# Power_Delivery.net
KiCad netlist of a schematic drawn in Altium Designer
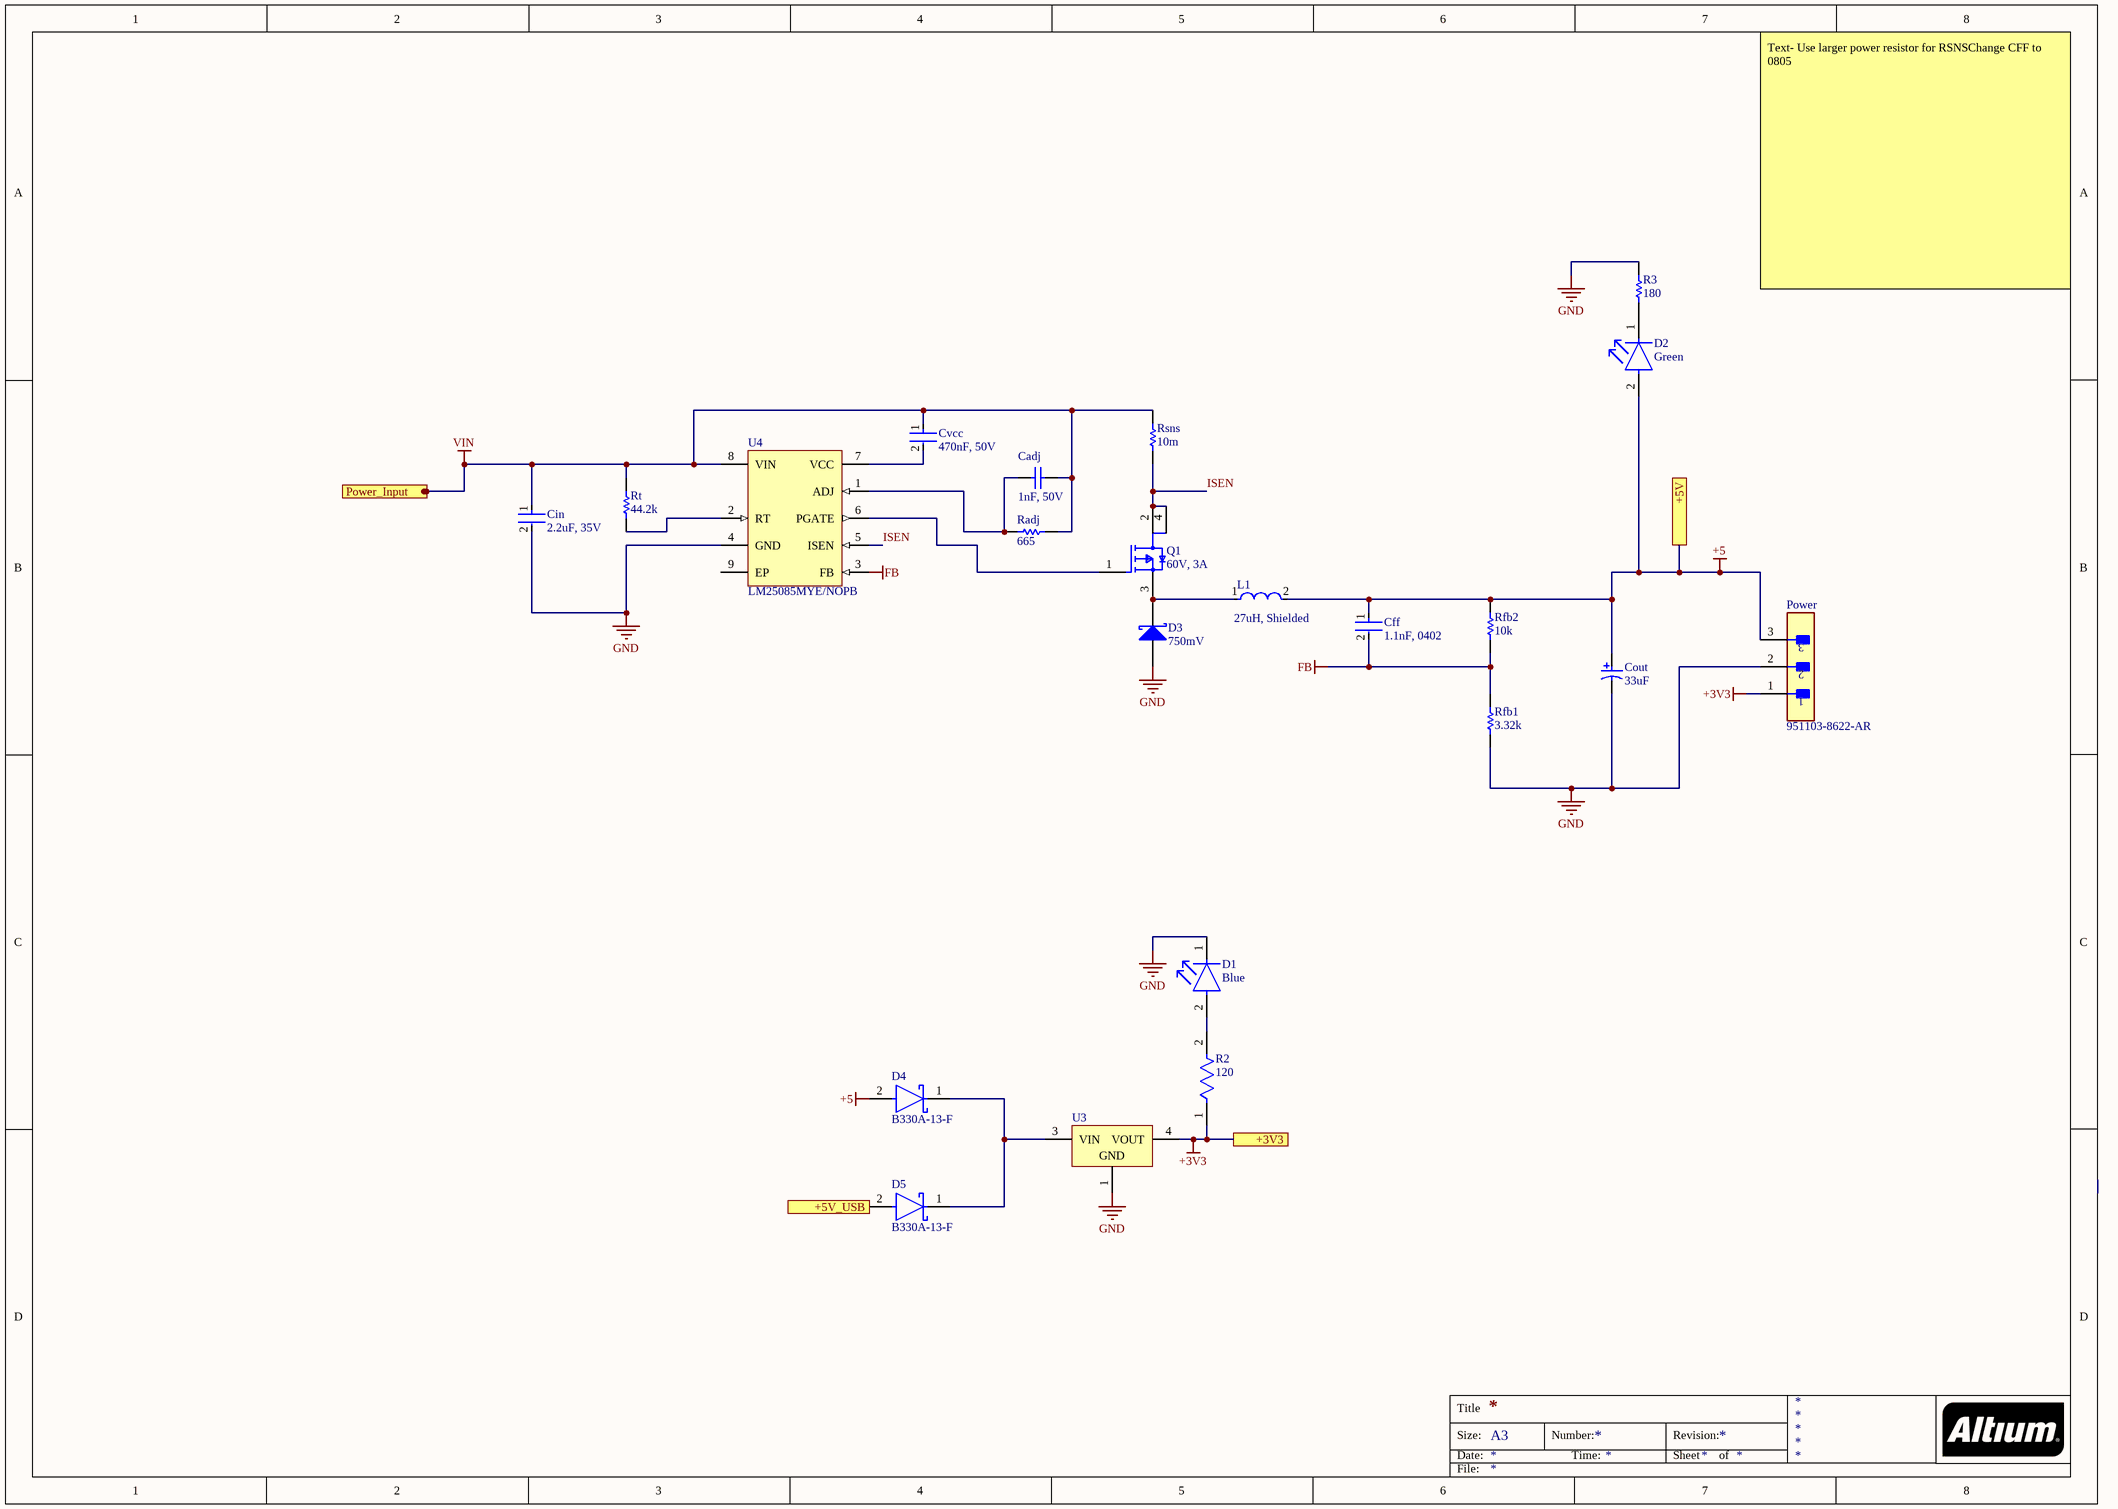
[diagram p0: Power Delivery.SchDoc]

(export (version "E")
  (design (tool "Eeschema 10.0.6"))
  (components
    (comp (ref "Cadj")
      (value "1nF, 50V")
      (footprint "CAPC2013X94X50ML20T25")
      (fields
        (field (name "PART NUMBER") "08055F102KAT2A")
        (field (name "MANUFACTURER") "AVX Interconnect / Elco")
      )
      (libsource (lib "Altium Content Vault") (part "CAP"))
    )
    (comp (ref "Cff")
      (value "1.1nF, 0402")
      (footprint "FP-C0402-BB-MFG")
      (description "CAP CER 1100PF 50V C0G/NP0 0402")
      (fields (field (name "MANUFACTURER PART NUMBER") "C0402C112J5GACTU") (field (name "TOLERANCE") "0.05"))
      (libsource (lib "Altium Content Vault") (part "b4654b650e69147ec39a6b967a45e02"))
    )
    (comp (ref "Cin")
      (value "2.2uF, 35V")
      (footprint "FP-C2012-125-0_2-IPC_B")
      (description "Multilayer Ceramic Capacitors 2.2μF ±10% 35V X6S SMD 0805")
      (fields (field (name "TOLERANCE") "10%"))
      (libsource (lib "Altium Content Vault") (part "b4654b650e69147ec39a6b967a45e02"))
    )
    (comp (ref "Cout")
      (value "33uF")
      (footprint "NIC-CAPA2-6.3X5.8_V")
      (fields (field (name "PARTNUMBER") "UUD1C330MCL1GS") (field (name "MANUFACTURER") "Nichicon"))
      (libsource (lib "Altium Content Vault") (part "NIC-CAP-P-2"))
    )
    (comp (ref "Cvcc")
      (value "470nF, 50V")
      (footprint "FP-GCM21B-0_15-IPC_A")
      (description "Ceramic Capacitor for Automotive 470nF ±10% 50VDC X7R 0805 Embossed T/R")
      (fields (field (name "TOLERANCE") "10%"))
      (libsource (lib "Altium Content Vault") (part "02cd4be3c70576c341d710602a673aa"))
    )
    (comp (ref "D1")
      (value "Blue")
      (footprint "FP-LTST-C191TBKT-MFG")
      (description "LED BLUE CLEAR CHIP SMD")
      (libsource (lib "Altium Content Vault") (part "8706943c75ba83719d021d2fdc84c58"))
    )
    (comp (ref "D2")
      (value "Green")
      (footprint "FP-6_541-5056_01-4-MFG")
      (description "LED GREEN 0603 SMD")
      (fields
        (field (name "MANUFACTURER PART NUMBER") "TLMP1100-GS08")
        (field (name "MANUFACTURER") "Vishay")
      )
      (libsource (lib "Altium Content Vault") (part "8706943c75ba83719d021d2fdc84c58"))
    )
    (comp (ref "D3")
      (value "750mV")
      (footprint "DIOD-SOD-323-2_V")
      (description "Schottky Barrier Diode, 30 V, -65 to 150 degC, 2-Pin SOD-323, RoHS, Tape and Reel")
      (fields (field (name "MANUFACTURER") "DiodesIncorporated"))
      (libsource (lib "Altium Content Vault") (part "DSKY-AK-2"))
    )
    (comp (ref "D4")
      (value "B330A-13-F")
      (footprint "FP-SMA-MFG")
      (description "DIODE SCHOTTKY 30V 3A SMA")
      (fields
        (field (name "OCTOPART") "https://octopart.com/b330a-13-f-diodes+inc.-325808")
        (field (name "MANUFACTURER") "Diodes")
      )
      (libsource (lib "Altium Content Vault") (part "1d6ec82d83fb6aee721767c19dac4b9"))
    )
    (comp (ref "D5")
      (value "B330A-13-F")
      (footprint "FP-SMA-MFG")
      (description "DIODE SCHOTTKY 30V 3A SMA")
      (fields
        (field (name "OCTOPART") "https://octopart.com/b330a-13-f-diodes+inc.-325808")
        (field (name "MANUFACTURER") "Diodes")
      )
      (libsource (lib "Altium Content Vault") (part "1d6ec82d83fb6aee721767c19dac4b9"))
    )
    (comp (ref "L1")
      (value "27uH, Shielded")
      (footprint "FP-SRR1260-MFG")
      (description "FIXED IND 27UH 3.6A 45 MOHM SMD")
      (fields (field (name "TOLERANCE") "20%") (field (name "MANUFACTURER PART NUMBER") "SRR1260-270M"))
      (libsource (lib "Altium Content Vault") (part "725321dda6339637d4d059423bc1c3c"))
    )
    (comp (ref "Power")
      (value "951103-8622-AR")
      (footprint "FP-951103-8622-AR-MFG")
      (description "CONN HEADER VERT 3POS 2MM")
      (fields
        (field (name "OCTOPART") "https://octopart.com/951103-8622-ar-3m-14400669")
        (field (name "MANUFACTURER") "3M")
      )
      (libsource (lib "Altium Content Vault") (part "0d3f023dd272f625e17a2be33dea85f"))
    )
    (comp (ref "Q1")
      (value "60V, 3A")
      (footprint "FP-SOT223-IPC_C")
      (description "MOSFET PCH 60V 3A SOT223")
      (libsource (lib "Altium Content Vault") (part "d648c27f595ee349eac043f81b2e06c"))
    )
    (comp (ref "R2")
      (value "120")
      (footprint "FP-AC0805-MFG")
      (description "RES SMD 120 OHM 5% 1/8W 0805")
      (fields
        (field (name "OCTOPART") "https://octopart.com/ac0805jr-07120rl-yageo-52448213")
        (field (name "TOLERANCE") "0.05")
      )
      (libsource (lib "Altium Content Vault") (part "1029c3af85768c4190bb7ad29bc67b5"))
    )
    (comp (ref "R3")
      (value "180")
      (footprint "RESC2013X70X40ML20T20")
      (fields (field (name "MANUFACTURER") "Panasonic") (field (name "PART NUMBER") "ERJ-6GEYJ181V"))
      (libsource (lib "Altium Content Vault") (part "RES"))
    )
    (comp (ref "Radj")
      (value "665")
      (footprint "RESC2013X70X40LL20T20")
      (description "Chip Resistor, 665 Ohm, +/- 1%, 0.125 W, -55 to 155 degC, 0805 (2012 Metric), RoHS, Tape and Reel")
      (fields (field (name "MANUFACTURER") "Panasonic"))
      (libsource (lib "Altium Content Vault") (part "RES-2"))
    )
    (comp (ref "Rfb1")
      (value "3.32k")
      (footprint "RESC2013X55X40NL15T20")
      (fields (field (name "PART NUMBER") "TNPW08053K32BEEN") (field (name "MANUFACTURER") "Vishay Dale"))
      (libsource (lib "Altium Content Vault") (part "RES"))
    )
    (comp (ref "Rfb2")
      (value "10k")
      (footprint "RESC2013X60X35NL10T20")
      (description "Chip Resistor, 10 KOhm, +/- 1%, 0.125 W, -55 to 155 degC, 0805 (2012 Metric), RoHS, Tape and Reel")
      (fields (field (name "MANUFACTURER") "Yageo"))
      (libsource (lib "Altium Content Vault") (part "RES-2"))
    )
    (comp (ref "Rsns")
      (value "10m")
      (footprint "RESC2013X60X35LL10T20")
      (fields (field (name "PART NUMBER") "RL0805FR-070R01L") (field (name "MANUFACTURER") "Yageo"))
      (libsource (lib "Altium Content Vault") (part "RES"))
    )
    (comp (ref "Rt")
      (value "44.2k")
      (footprint "RESC2013X50X30LL20T20")
      (fields (field (name "PART NUMBER") "CRCW080544K2FKEA") (field (name "MANUFACTURER") "Vishay Dale"))
      (libsource (lib "Altium Content Vault") (part "RES"))
    )
    (comp (ref "U3")
      (value "~")
      (footprint "TO-252_N")
      (description "Fixed Low Drop Positive Voltage Regulator, 3.3V, 3-Pin DPAK, Tape and Reel")
      (libsource (lib "Altium Content Vault") (part "PM-REG-LD1117-SOT3"))
    )
    (comp (ref "U4")
      (value "LM25085MYE/NOPB")
      (footprint "DGN0008A_L")
      (description "42V Constant On-Time PFET Buck Switching Controller, 8-pin eMSOP, Pb-Free")
      (fields (field (name "MANUFACTURER") "Texas Instruments"))
      (libsource (lib "Altium Content Vault") (part "PM-SWREG-LM25085-IL9"))
    )
  )
  (nets
    (net (code "1") (name "+3V3") (class "Default")
      (node (ref "Power") (pin "1") (pinfunction "1_1") (pintype "passive"))
      (node (ref "R2") (pin "1") (pinfunction "1_1") (pintype "passive"))
      (node (ref "U3") (pin "4") (pinfunction "VOUT_4") (pintype "power_in"))
    )
    (net (code "2") (name "+5") (class "Default")
      (node (ref "Cff") (pin "1") (pinfunction "1_1") (pintype "passive"))
      (node (ref "Cout") (pin "1") (pinfunction "1_1") (pintype "passive"))
      (node (ref "D2") (pin "2") (pinfunction "A_2") (pintype "passive"))
      (node (ref "D4") (pin "2") (pinfunction "A_2") (pintype "passive"))
      (node (ref "L1") (pin "2") (pinfunction "2_2") (pintype "passive"))
      (node (ref "Power") (pin "3") (pinfunction "3_3") (pintype "passive"))
      (node (ref "Rfb2") (pin "2") (pinfunction "2_2") (pintype "passive"))
    )
    (net (code "3") (name "/+5V_USB") (class "Default")
      (node (ref "D5") (pin "2") (pinfunction "A_2") (pintype "passive"))
    )
    (net (code "4") (name "/ISEN") (class "Default")
      (node (ref "Q1") (pin "2") (pinfunction "D_2") (pintype "passive"))
      (node (ref "Q1") (pin "4") (pinfunction "D_4") (pintype "passive"))
      (node (ref "Rsns") (pin "1") (pinfunction "1_1") (pintype "passive"))
      (node (ref "U4") (pin "5") (pinfunction "ISEN_5") (pintype "input"))
    )
    (net (code "5") (name "FB") (class "Default")
      (node (ref "Cff") (pin "2") (pinfunction "2_2") (pintype "passive"))
      (node (ref "Rfb1") (pin "2") (pinfunction "2_2") (pintype "passive"))
      (node (ref "Rfb2") (pin "1") (pinfunction "1_1") (pintype "passive"))
      (node (ref "U4") (pin "3") (pinfunction "FB_3") (pintype "input"))
    )
    (net (code "6") (name "GND") (class "Default")
      (node (ref "Cin") (pin "2") (pinfunction "2_2") (pintype "passive"))
      (node (ref "Cout") (pin "2") (pinfunction "2_2") (pintype "passive"))
      (node (ref "D1") (pin "1") (pinfunction "C_1") (pintype "passive"))
      (node (ref "D3") (pin "1") (pinfunction "A_1") (pintype "passive"))
      (node (ref "Power") (pin "2") (pinfunction "2_2") (pintype "passive"))
      (node (ref "R3") (pin "2") (pinfunction "2_2") (pintype "passive"))
      (node (ref "Rfb1") (pin "1") (pinfunction "1_1") (pintype "passive"))
      (node (ref "U3") (pin "1") (pinfunction "GND_1") (pintype "power_in"))
      (node (ref "U4") (pin "4") (pinfunction "GND_4") (pintype "power_in"))
    )
    (net (code "7") (name "Net-(D1-A)") (class "Default")
      (node (ref "D1") (pin "2") (pinfunction "A_2") (pintype "passive"))
      (node (ref "R2") (pin "2") (pinfunction "2_2") (pintype "passive"))
    )
    (net (code "8") (name "Net-(D2-C)") (class "Default")
      (node (ref "D2") (pin "1") (pinfunction "C_1") (pintype "passive"))
      (node (ref "R3") (pin "1") (pinfunction "1_1") (pintype "passive"))
    )
    (net (code "9") (name "Net-(D3-K)") (class "Default")
      (node (ref "D3") (pin "2") (pinfunction "K_2") (pintype "passive"))
      (node (ref "L1") (pin "1") (pinfunction "1_1") (pintype "passive"))
      (node (ref "Q1") (pin "3") (pinfunction "S_3") (pintype "passive"))
    )
    (net (code "10") (name "Net-(D4-C)") (class "Default")
      (node (ref "D4") (pin "1") (pinfunction "C_1") (pintype "passive"))
      (node (ref "D5") (pin "1") (pinfunction "C_1") (pintype "passive"))
      (node (ref "U3") (pin "3") (pinfunction "VIN_3") (pintype "power_in"))
    )
    (net (code "11") (name "Net-(Q1-G)") (class "Default")
      (node (ref "Q1") (pin "1") (pinfunction "G_1") (pintype "passive"))
      (node (ref "U4") (pin "6") (pinfunction "PGATE_6") (pintype "output"))
    )
    (net (code "12") (name "Net-(U4-ADJ)") (class "Default")
      (node (ref "Cadj") (pin "2") (pinfunction "2_2") (pintype "passive"))
      (node (ref "Radj") (pin "1") (pinfunction "1_1") (pintype "passive"))
      (node (ref "U4") (pin "1") (pinfunction "ADJ_1") (pintype "input"))
    )
    (net (code "13") (name "Net-(U4-RT)") (class "Default")
      (node (ref "Rt") (pin "1") (pinfunction "1_1") (pintype "passive"))
      (node (ref "U4") (pin "2") (pinfunction "RT_2") (pintype "input"))
    )
    (net (code "14") (name "Net-(U4-VCC)") (class "Default")
      (node (ref "Cvcc") (pin "2") (pinfunction "2_2") (pintype "passive"))
      (node (ref "U4") (pin "7") (pinfunction "VCC_7") (pintype "power_in"))
    )
    (net (code "15") (name "VIN") (class "Default")
      (node (ref "Cadj") (pin "1") (pinfunction "1_1") (pintype "passive"))
      (node (ref "Cin") (pin "1") (pinfunction "1_1") (pintype "passive"))
      (node (ref "Cvcc") (pin "1") (pinfunction "1_1") (pintype "passive"))
      (node (ref "Radj") (pin "2") (pinfunction "2_2") (pintype "passive"))
      (node (ref "Rsns") (pin "2") (pinfunction "2_2") (pintype "passive"))
      (node (ref "Rt") (pin "2") (pinfunction "2_2") (pintype "passive"))
      (node (ref "U4") (pin "8") (pinfunction "VIN_8") (pintype "power_in"))
    )
    (net (code "16") (name "unconnected-(U4-EP-Pad9)") (class "Default")
      (node (ref "U4") (pin "9") (pinfunction "EP_9") (pintype "power_in"))
    )
  )
)
